# 555-piano-pad.net
KiCad netlist of a schematic drawn in EAGLE
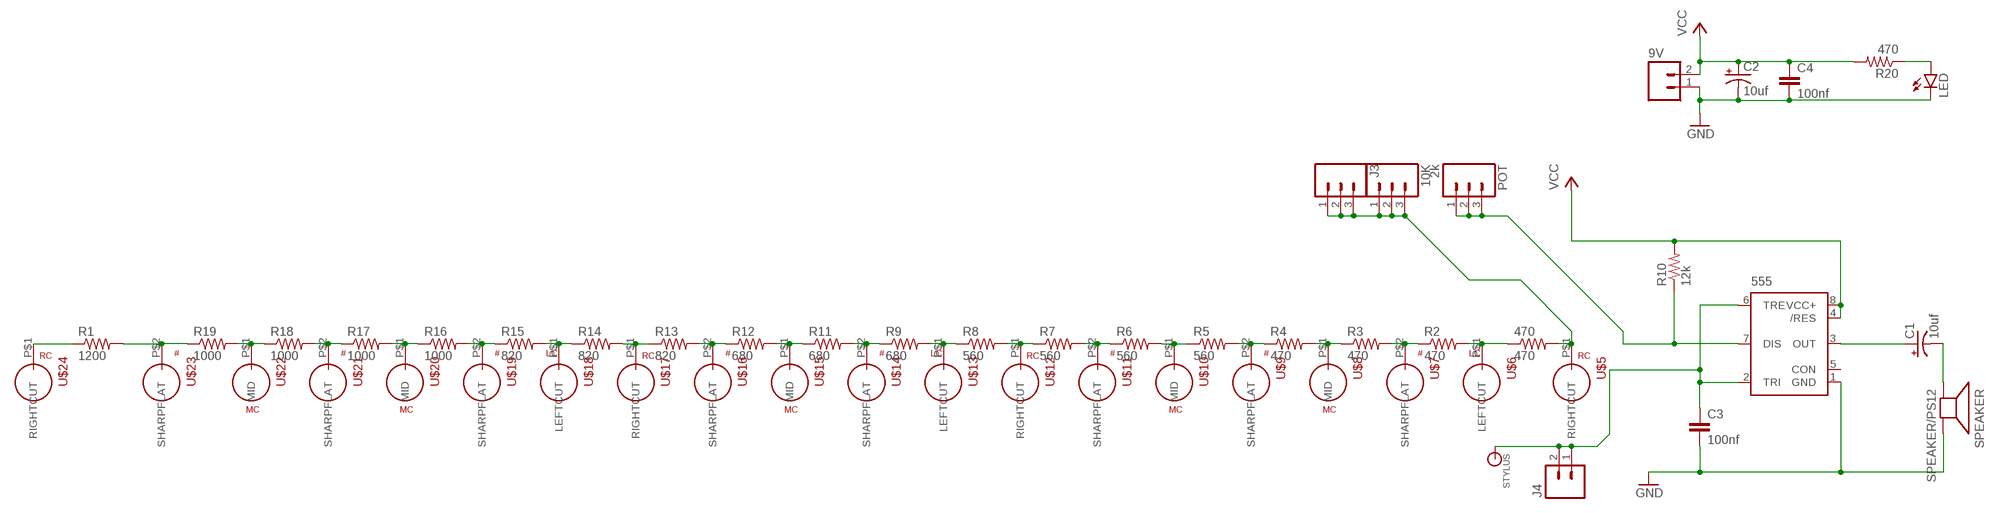
[diagram p0: schematic, sheet 1]

(export (version "E")
  (design (tool "Eeschema 10.0.6"))
  (components
    (comp (ref "9V")
      (value "M02PTH3")
      (footprint "eagle-import:1X02_LONGPADS")
      (libsource (lib "eagle-import") (part "M02PTH3"))
    )
    (comp (ref "10K")
      (value "M03PTH")
      (footprint "eagle-import:1X03")
      (libsource (lib "eagle-import") (part "M03PTH"))
    )
    (comp (ref "470")
      (value "470")
      (footprint "eagle-import:AXIAL-0.3")
      (libsource (lib "eagle-import") (part "RESISTORAXIAL-0.3"))
    )
    (comp (ref "555")
      (value "NE555P")
      (footprint "eagle-import:DIL-08")
      (fields (field (name "MF") "Arrow Electronics") (field (name "MPN") "NE555N"))
      (libsource (lib "eagle-import") (part "NE555P"))
    )
    (comp (ref "C1")
      (value "10uf")
      (footprint "eagle-import:CPOL-RADIAL-10UF-25V")
      (libsource (lib "eagle-import") (part "10UF-25V-20%(PTH)"))
    )
    (comp (ref "C2")
      (value "10uf")
      (footprint "eagle-import:CPOL-RADIAL-10UF-25V")
      (libsource (lib "eagle-import") (part "10UF-25V-20%(PTH)"))
    )
    (comp (ref "C3")
      (value "100nf")
      (footprint "eagle-import:CAP-PTH-SMALL2")
      (libsource (lib "eagle-import") (part "CAPPTH2"))
    )
    (comp (ref "C4")
      (value "100nf")
      (footprint "eagle-import:CAP-PTH-SMALL2")
      (libsource (lib "eagle-import") (part "CAPPTH2"))
    )
    (comp (ref "J3")
      (value "M03PTH")
      (footprint "eagle-import:1X03")
      (libsource (lib "eagle-import") (part "M03PTH"))
    )
    (comp (ref "J4")
      (value "M02PTH3")
      (footprint "eagle-import:1X02_LONGPADS")
      (libsource (lib "eagle-import") (part "M02PTH3"))
    )
    (comp (ref "LED")
      (value "LED5MM")
      (footprint "eagle-import:LED5MM")
      (libsource (lib "eagle-import") (part "LED5MM"))
    )
    (comp (ref "POT")
      (value "2k")
      (footprint "eagle-import:1X03")
      (libsource (lib "eagle-import") (part "M03PTH"))
    )
    (comp (ref "R1")
      (value "1200")
      (footprint "eagle-import:AXIAL-0.3")
      (libsource (lib "eagle-import") (part "RESISTORAXIAL-0.3"))
    )
    (comp (ref "R2")
      (value "470")
      (footprint "eagle-import:AXIAL-0.3")
      (libsource (lib "eagle-import") (part "RESISTORAXIAL-0.3"))
    )
    (comp (ref "R3")
      (value "470")
      (footprint "eagle-import:AXIAL-0.3")
      (libsource (lib "eagle-import") (part "RESISTORAXIAL-0.3"))
    )
    (comp (ref "R4")
      (value "470")
      (footprint "eagle-import:AXIAL-0.3")
      (libsource (lib "eagle-import") (part "RESISTORAXIAL-0.3"))
    )
    (comp (ref "R5")
      (value "560")
      (footprint "eagle-import:AXIAL-0.3")
      (libsource (lib "eagle-import") (part "RESISTORAXIAL-0.3"))
    )
    (comp (ref "R6")
      (value "560")
      (footprint "eagle-import:AXIAL-0.3")
      (libsource (lib "eagle-import") (part "RESISTORAXIAL-0.3"))
    )
    (comp (ref "R7")
      (value "560")
      (footprint "eagle-import:AXIAL-0.3")
      (libsource (lib "eagle-import") (part "RESISTORAXIAL-0.3"))
    )
    (comp (ref "R8")
      (value "560")
      (footprint "eagle-import:AXIAL-0.3")
      (libsource (lib "eagle-import") (part "RESISTORAXIAL-0.3"))
    )
    (comp (ref "R9")
      (value "680")
      (footprint "eagle-import:AXIAL-0.3")
      (libsource (lib "eagle-import") (part "RESISTORAXIAL-0.3"))
    )
    (comp (ref "R10")
      (value "12k")
      (footprint "eagle-import:AXIAL-0.3")
      (libsource (lib "eagle-import") (part "RESISTORAXIAL-0.3"))
    )
    (comp (ref "R11")
      (value "680")
      (footprint "eagle-import:AXIAL-0.3")
      (libsource (lib "eagle-import") (part "RESISTORAXIAL-0.3"))
    )
    (comp (ref "R12")
      (value "680")
      (footprint "eagle-import:AXIAL-0.3")
      (libsource (lib "eagle-import") (part "RESISTORAXIAL-0.3"))
    )
    (comp (ref "R13")
      (value "820")
      (footprint "eagle-import:AXIAL-0.3")
      (libsource (lib "eagle-import") (part "RESISTORAXIAL-0.3"))
    )
    (comp (ref "R14")
      (value "820")
      (footprint "eagle-import:AXIAL-0.3")
      (libsource (lib "eagle-import") (part "RESISTORAXIAL-0.3"))
    )
    (comp (ref "R15")
      (value "820")
      (footprint "eagle-import:AXIAL-0.3")
      (libsource (lib "eagle-import") (part "RESISTORAXIAL-0.3"))
    )
    (comp (ref "R16")
      (value "1000")
      (footprint "eagle-import:AXIAL-0.3")
      (libsource (lib "eagle-import") (part "RESISTORAXIAL-0.3"))
    )
    (comp (ref "R17")
      (value "1000")
      (footprint "eagle-import:AXIAL-0.3")
      (libsource (lib "eagle-import") (part "RESISTORAXIAL-0.3"))
    )
    (comp (ref "R18")
      (value "1000")
      (footprint "eagle-import:AXIAL-0.3")
      (libsource (lib "eagle-import") (part "RESISTORAXIAL-0.3"))
    )
    (comp (ref "R19")
      (value "1000")
      (footprint "eagle-import:AXIAL-0.3")
      (libsource (lib "eagle-import") (part "RESISTORAXIAL-0.3"))
    )
    (comp (ref "R20")
      (value "470")
      (footprint "eagle-import:AXIAL-0.3")
      (libsource (lib "eagle-import") (part "RESISTORAXIAL-0.3"))
    )
    (comp (ref "SPEAKER")
      (value "SPEAKER/PS12")
      (footprint "eagle-import:PS12")
      (libsource (lib "eagle-import") (part "SPEAKER/PS12"))
    )
    (comp (ref "STYLUS")
      (value "BANANA_CONN")
      (footprint "eagle-import:BANANA_CONN")
      (libsource (lib "eagle-import") (part "BANANA_CONN"))
    )
    (comp (ref "U$5")
      (value "PINANO-RIGHT-CUT")
      (footprint "eagle-import:PINANO-RIGHT-CUT")
      (libsource (lib "eagle-import") (part "PINANO-RIGHT-CUT"))
    )
    (comp (ref "U$6")
      (value "PINANO-LEFT-CUT")
      (footprint "eagle-import:PINANO-LEFT-CUT")
      (libsource (lib "eagle-import") (part "PINANO-LEFT-CUT"))
    )
    (comp (ref "U$7")
      (value "PINANO-SHARPFLAT")
      (footprint "eagle-import:PINANO-SHARPFLAT")
      (libsource (lib "eagle-import") (part "PINANO-SHARPFLAT"))
    )
    (comp (ref "U$8")
      (value "PINANO-MID")
      (footprint "eagle-import:PINANO-MID")
      (libsource (lib "eagle-import") (part "PINANO-MID"))
    )
    (comp (ref "U$9")
      (value "PINANO-SHARPFLAT")
      (footprint "eagle-import:PINANO-SHARPFLAT")
      (libsource (lib "eagle-import") (part "PINANO-SHARPFLAT"))
    )
    (comp (ref "U$10")
      (value "PINANO-MID")
      (footprint "eagle-import:PINANO-MID")
      (libsource (lib "eagle-import") (part "PINANO-MID"))
    )
    (comp (ref "U$11")
      (value "PINANO-SHARPFLAT")
      (footprint "eagle-import:PINANO-SHARPFLAT")
      (libsource (lib "eagle-import") (part "PINANO-SHARPFLAT"))
    )
    (comp (ref "U$12")
      (value "PINANO-RIGHT-CUT")
      (footprint "eagle-import:PINANO-RIGHT-CUT")
      (libsource (lib "eagle-import") (part "PINANO-RIGHT-CUT"))
    )
    (comp (ref "U$13")
      (value "PINANO-LEFT-CUT")
      (footprint "eagle-import:PINANO-LEFT-CUT")
      (libsource (lib "eagle-import") (part "PINANO-LEFT-CUT"))
    )
    (comp (ref "U$14")
      (value "PINANO-SHARPFLAT")
      (footprint "eagle-import:PINANO-SHARPFLAT")
      (libsource (lib "eagle-import") (part "PINANO-SHARPFLAT"))
    )
    (comp (ref "U$15")
      (value "PINANO-MID")
      (footprint "eagle-import:PINANO-MID")
      (libsource (lib "eagle-import") (part "PINANO-MID"))
    )
    (comp (ref "U$16")
      (value "PINANO-SHARPFLAT")
      (footprint "eagle-import:PINANO-SHARPFLAT")
      (libsource (lib "eagle-import") (part "PINANO-SHARPFLAT"))
    )
    (comp (ref "U$17")
      (value "PINANO-RIGHT-CUT")
      (footprint "eagle-import:PINANO-RIGHT-CUT")
      (libsource (lib "eagle-import") (part "PINANO-RIGHT-CUT"))
    )
    (comp (ref "U$18")
      (value "PINANO-LEFT-CUT")
      (footprint "eagle-import:PINANO-LEFT-CUT")
      (libsource (lib "eagle-import") (part "PINANO-LEFT-CUT"))
    )
    (comp (ref "U$19")
      (value "PINANO-SHARPFLAT")
      (footprint "eagle-import:PINANO-SHARPFLAT")
      (libsource (lib "eagle-import") (part "PINANO-SHARPFLAT"))
    )
    (comp (ref "U$20")
      (value "PINANO-MID")
      (footprint "eagle-import:PINANO-MID")
      (libsource (lib "eagle-import") (part "PINANO-MID"))
    )
    (comp (ref "U$21")
      (value "PINANO-SHARPFLAT")
      (footprint "eagle-import:PINANO-SHARPFLAT")
      (libsource (lib "eagle-import") (part "PINANO-SHARPFLAT"))
    )
    (comp (ref "U$22")
      (value "PINANO-MID")
      (footprint "eagle-import:PINANO-MID")
      (libsource (lib "eagle-import") (part "PINANO-MID"))
    )
    (comp (ref "U$23")
      (value "PINANO-SHARPFLAT")
      (footprint "eagle-import:PINANO-SHARPFLAT")
      (libsource (lib "eagle-import") (part "PINANO-SHARPFLAT"))
    )
    (comp (ref "U$24")
      (value "PINANO-RIGHT-CUT")
      (footprint "eagle-import:PINANO-RIGHT-CUT")
      (libsource (lib "eagle-import") (part "PINANO-RIGHT-CUT"))
    )
  )
  (nets
    (net (code "1") (name "GND") (class "Default")
      (node (ref "555") (pin "1") (pinfunction "GND_1") (pintype "power_in"))
      (node (ref "9V") (pin "1") (pinfunction "1_1") (pintype "passive"))
      (node (ref "C2") (pin "2") (pinfunction "-_2") (pintype "passive"))
      (node (ref "C3") (pin "2") (pinfunction "2_2") (pintype "passive"))
      (node (ref "C4") (pin "2") (pinfunction "2_2") (pintype "passive"))
      (node (ref "LED") (pin "K") (pinfunction "C_K") (pintype "passive"))
      (node (ref "SPEAKER") (pin "P$2") (pinfunction "-_P$2") (pintype "passive"))
    )
    (net (code "2") (name "Net-(470-1)") (class "Default")
      (node (ref "470") (pin "P$1") (pinfunction "1_P$1") (pintype "passive"))
      (node (ref "R2") (pin "P$2") (pinfunction "2_P$2") (pintype "passive"))
      (node (ref "U$6") (pin "P$1") (pinfunction "LEFTCUT_P$1") (pintype "bidirectional"))
    )
    (net (code "3") (name "Net-(470-2)") (class "Default")
      (node (ref "10K") (pin "1") (pinfunction "1_1") (pintype "passive"))
      (node (ref "10K") (pin "2") (pinfunction "2_2") (pintype "passive"))
      (node (ref "10K") (pin "3") (pinfunction "3_3") (pintype "passive"))
      (node (ref "470") (pin "P$2") (pinfunction "2_P$2") (pintype "passive"))
      (node (ref "J3") (pin "1") (pinfunction "1_1") (pintype "passive"))
      (node (ref "J3") (pin "2") (pinfunction "2_2") (pintype "passive"))
      (node (ref "J3") (pin "3") (pinfunction "3_3") (pintype "passive"))
      (node (ref "U$5") (pin "P$1") (pinfunction "RIGHTCUT_P$1") (pintype "bidirectional"))
    )
    (net (code "4") (name "Net-(555-DIS)") (class "Default")
      (node (ref "555") (pin "7") (pinfunction "DIS_7") (pintype "input"))
      (node (ref "POT") (pin "1") (pinfunction "1_1") (pintype "passive"))
      (node (ref "POT") (pin "2") (pinfunction "2_2") (pintype "passive"))
      (node (ref "POT") (pin "3") (pinfunction "3_3") (pintype "passive"))
      (node (ref "R10") (pin "P$1") (pinfunction "1_P$1") (pintype "passive"))
    )
    (net (code "5") (name "Net-(555-OUT)") (class "Default")
      (node (ref "555") (pin "3") (pinfunction "OUT_3") (pintype "output"))
      (node (ref "C1") (pin "1") (pinfunction "+_1") (pintype "passive"))
    )
    (net (code "6") (name "Net-(555-TRE)") (class "Default")
      (node (ref "555") (pin "2") (pinfunction "TRI_2") (pintype "input"))
      (node (ref "555") (pin "6") (pinfunction "TRE_6") (pintype "input"))
      (node (ref "C3") (pin "1") (pinfunction "1_1") (pintype "passive"))
      (node (ref "J4") (pin "1") (pinfunction "1_1") (pintype "passive"))
      (node (ref "J4") (pin "2") (pinfunction "2_2") (pintype "passive"))
      (node (ref "STYLUS") (pin "P$1") (pinfunction "1_P$1") (pintype "passive"))
    )
    (net (code "7") (name "Net-(C1--)") (class "Default")
      (node (ref "C1") (pin "2") (pinfunction "-_2") (pintype "passive"))
      (node (ref "SPEAKER") (pin "P$1") (pinfunction "+_P$1") (pintype "passive"))
    )
    (net (code "8") (name "Net-(R1-1)") (class "Default")
      (node (ref "R1") (pin "P$1") (pinfunction "1_P$1") (pintype "passive"))
      (node (ref "U$24") (pin "P$1") (pinfunction "RIGHTCUT_P$1") (pintype "bidirectional"))
    )
    (net (code "9") (name "Net-(R1-2)") (class "Default")
      (node (ref "R1") (pin "P$2") (pinfunction "2_P$2") (pintype "passive"))
      (node (ref "R19") (pin "P$1") (pinfunction "1_P$1") (pintype "passive"))
      (node (ref "U$23") (pin "P$2") (pinfunction "SHARPFLAT_P$2") (pintype "bidirectional"))
    )
    (net (code "10") (name "Net-(R2-1)") (class "Default")
      (node (ref "R2") (pin "P$1") (pinfunction "1_P$1") (pintype "passive"))
      (node (ref "R3") (pin "P$2") (pinfunction "2_P$2") (pintype "passive"))
      (node (ref "U$7") (pin "P$2") (pinfunction "SHARPFLAT_P$2") (pintype "bidirectional"))
    )
    (net (code "11") (name "Net-(R3-1)") (class "Default")
      (node (ref "R3") (pin "P$1") (pinfunction "1_P$1") (pintype "passive"))
      (node (ref "R4") (pin "P$2") (pinfunction "2_P$2") (pintype "passive"))
      (node (ref "U$8") (pin "P$1") (pinfunction "MID_P$1") (pintype "bidirectional"))
    )
    (net (code "12") (name "Net-(R4-1)") (class "Default")
      (node (ref "R4") (pin "P$1") (pinfunction "1_P$1") (pintype "passive"))
      (node (ref "R5") (pin "P$2") (pinfunction "2_P$2") (pintype "passive"))
      (node (ref "U$9") (pin "P$2") (pinfunction "SHARPFLAT_P$2") (pintype "bidirectional"))
    )
    (net (code "13") (name "Net-(R5-1)") (class "Default")
      (node (ref "R5") (pin "P$1") (pinfunction "1_P$1") (pintype "passive"))
      (node (ref "R6") (pin "P$2") (pinfunction "2_P$2") (pintype "passive"))
      (node (ref "U$10") (pin "P$1") (pinfunction "MID_P$1") (pintype "bidirectional"))
    )
    (net (code "14") (name "Net-(R6-1)") (class "Default")
      (node (ref "R6") (pin "P$1") (pinfunction "1_P$1") (pintype "passive"))
      (node (ref "R7") (pin "P$2") (pinfunction "2_P$2") (pintype "passive"))
      (node (ref "U$11") (pin "P$2") (pinfunction "SHARPFLAT_P$2") (pintype "bidirectional"))
    )
    (net (code "15") (name "Net-(R7-1)") (class "Default")
      (node (ref "R7") (pin "P$1") (pinfunction "1_P$1") (pintype "passive"))
      (node (ref "R8") (pin "P$2") (pinfunction "2_P$2") (pintype "passive"))
      (node (ref "U$12") (pin "P$1") (pinfunction "RIGHTCUT_P$1") (pintype "bidirectional"))
    )
    (net (code "16") (name "Net-(R8-1)") (class "Default")
      (node (ref "R8") (pin "P$1") (pinfunction "1_P$1") (pintype "passive"))
      (node (ref "R9") (pin "P$2") (pinfunction "2_P$2") (pintype "passive"))
      (node (ref "U$13") (pin "P$1") (pinfunction "LEFTCUT_P$1") (pintype "bidirectional"))
    )
    (net (code "17") (name "Net-(R11-1)") (class "Default")
      (node (ref "R11") (pin "P$1") (pinfunction "1_P$1") (pintype "passive"))
      (node (ref "R12") (pin "P$2") (pinfunction "2_P$2") (pintype "passive"))
      (node (ref "U$15") (pin "P$1") (pinfunction "MID_P$1") (pintype "bidirectional"))
    )
    (net (code "18") (name "Net-(R11-2)") (class "Default")
      (node (ref "R11") (pin "P$2") (pinfunction "2_P$2") (pintype "passive"))
      (node (ref "R9") (pin "P$1") (pinfunction "1_P$1") (pintype "passive"))
      (node (ref "U$14") (pin "P$2") (pinfunction "SHARPFLAT_P$2") (pintype "bidirectional"))
    )
    (net (code "19") (name "Net-(R12-1)") (class "Default")
      (node (ref "R12") (pin "P$1") (pinfunction "1_P$1") (pintype "passive"))
      (node (ref "R13") (pin "P$2") (pinfunction "2_P$2") (pintype "passive"))
      (node (ref "U$16") (pin "P$2") (pinfunction "SHARPFLAT_P$2") (pintype "bidirectional"))
    )
    (net (code "20") (name "Net-(R13-1)") (class "Default")
      (node (ref "R13") (pin "P$1") (pinfunction "1_P$1") (pintype "passive"))
      (node (ref "R14") (pin "P$2") (pinfunction "2_P$2") (pintype "passive"))
      (node (ref "U$17") (pin "P$1") (pinfunction "RIGHTCUT_P$1") (pintype "bidirectional"))
    )
    (net (code "21") (name "Net-(R14-1)") (class "Default")
      (node (ref "R14") (pin "P$1") (pinfunction "1_P$1") (pintype "passive"))
      (node (ref "R15") (pin "P$2") (pinfunction "2_P$2") (pintype "passive"))
      (node (ref "U$18") (pin "P$1") (pinfunction "LEFTCUT_P$1") (pintype "bidirectional"))
    )
    (net (code "22") (name "Net-(R15-1)") (class "Default")
      (node (ref "R15") (pin "P$1") (pinfunction "1_P$1") (pintype "passive"))
      (node (ref "R16") (pin "P$2") (pinfunction "2_P$2") (pintype "passive"))
      (node (ref "U$19") (pin "P$2") (pinfunction "SHARPFLAT_P$2") (pintype "bidirectional"))
    )
    (net (code "23") (name "Net-(R16-1)") (class "Default")
      (node (ref "R16") (pin "P$1") (pinfunction "1_P$1") (pintype "passive"))
      (node (ref "R17") (pin "P$2") (pinfunction "2_P$2") (pintype "passive"))
      (node (ref "U$20") (pin "P$1") (pinfunction "MID_P$1") (pintype "bidirectional"))
    )
    (net (code "24") (name "Net-(R17-1)") (class "Default")
      (node (ref "R17") (pin "P$1") (pinfunction "1_P$1") (pintype "passive"))
      (node (ref "R18") (pin "P$2") (pinfunction "2_P$2") (pintype "passive"))
      (node (ref "U$21") (pin "P$2") (pinfunction "SHARPFLAT_P$2") (pintype "bidirectional"))
    )
    (net (code "25") (name "Net-(R18-1)") (class "Default")
      (node (ref "R18") (pin "P$1") (pinfunction "1_P$1") (pintype "passive"))
      (node (ref "R19") (pin "P$2") (pinfunction "2_P$2") (pintype "passive"))
      (node (ref "U$22") (pin "P$1") (pinfunction "MID_P$1") (pintype "bidirectional"))
    )
    (net (code "26") (name "Net-(R20-1)") (class "Default")
      (node (ref "LED") (pin "A") (pinfunction "A_A") (pintype "passive"))
      (node (ref "R20") (pin "P$1") (pinfunction "1_P$1") (pintype "passive"))
    )
    (net (code "27") (name "VCC") (class "Default")
      (node (ref "555") (pin "4") (pinfunction "/RES_4") (pintype "input"))
      (node (ref "555") (pin "8") (pinfunction "VCC+_8") (pintype "power_in"))
      (node (ref "9V") (pin "2") (pinfunction "2_2") (pintype "passive"))
      (node (ref "C2") (pin "1") (pinfunction "+_1") (pintype "passive"))
      (node (ref "C4") (pin "1") (pinfunction "1_1") (pintype "passive"))
      (node (ref "R10") (pin "P$2") (pinfunction "2_P$2") (pintype "passive"))
      (node (ref "R20") (pin "P$2") (pinfunction "2_P$2") (pintype "passive"))
    )
    (net (code "28") (name "unconnected-(555-CON-Pad5)") (class "Default")
      (node (ref "555") (pin "5") (pinfunction "CON_5") (pintype "input"))
    )
  )
)
